# 08_LMS1_RF.net
KiCad netlist of a schematic drawn in Altium Designer
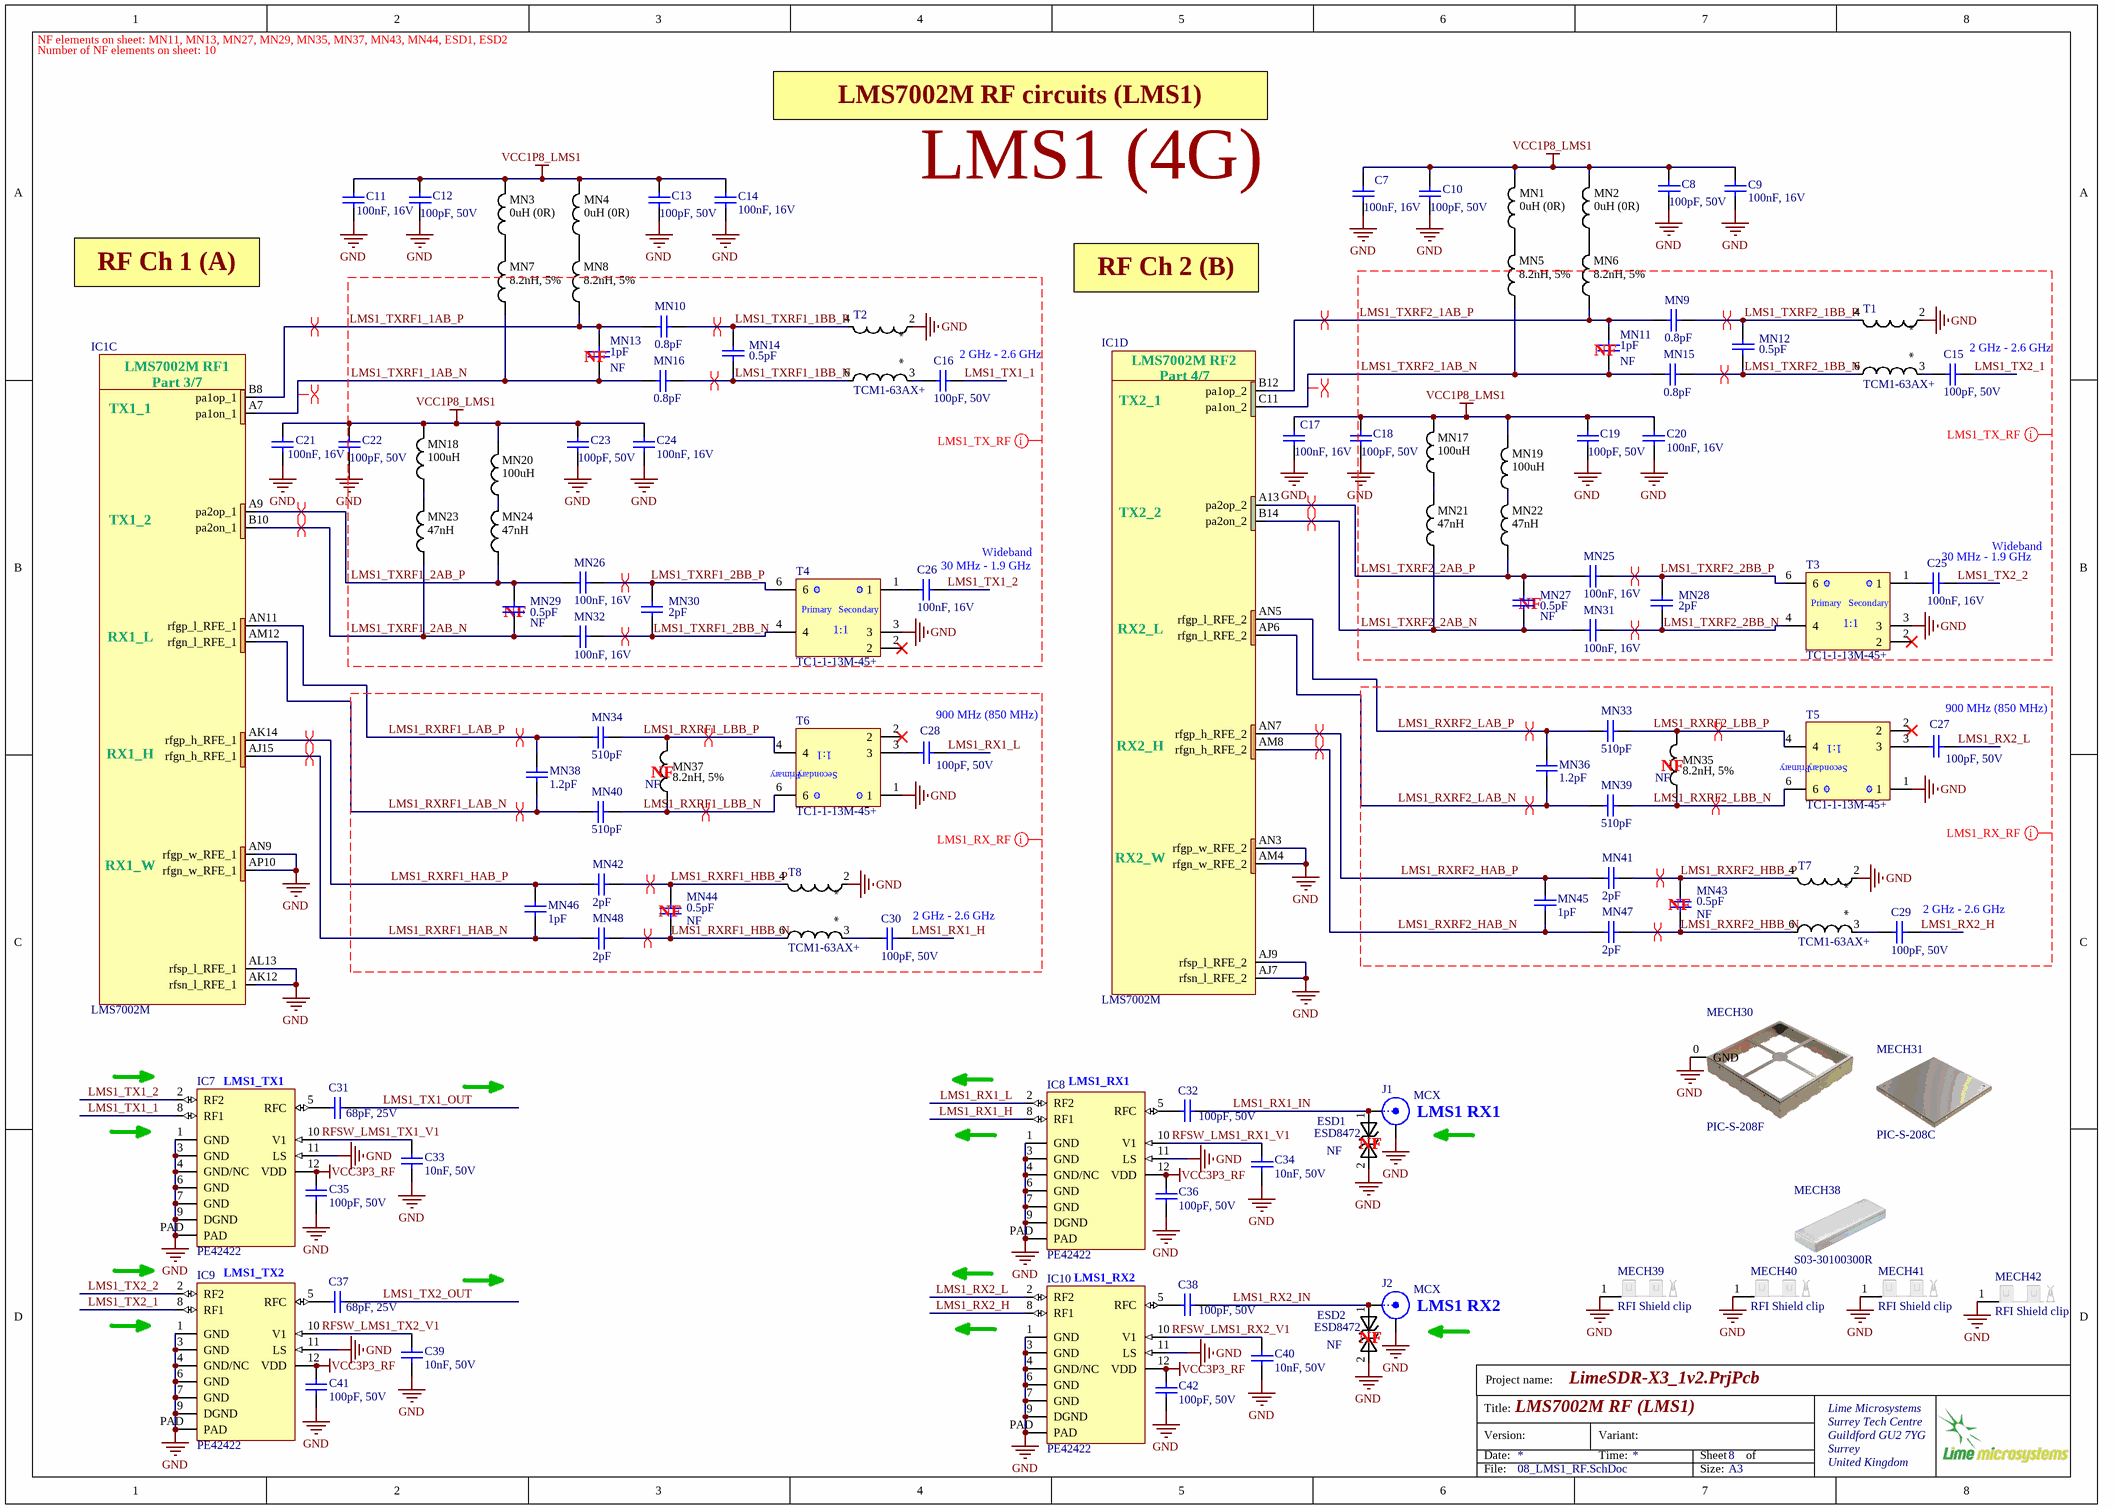
[diagram p0: 08_LMS1_RF.SchDoc]

(export (version "E")
  (design (tool "Eeschema 10.0.6"))
  (components
    (comp (ref "C7")
      (value "100nF, 16V")
      (footprint "CAP0402")
      (fields (field (name "MANUFACTURER") "Murata Electronics") (field (name "TOLERANCE") "10 %"))
      (libsource (lib "") (part "Cap_0402_4"))
    )
    (comp (ref "C8")
      (value "100pF, 50V")
      (footprint "CAP0402")
      (fields (field (name "MANUFACTURER") "Yageo") (field (name "TOLERANCE") "±5%"))
      (libsource (lib "") (part "Cap_0402_3"))
    )
    (comp (ref "C9")
      (value "100nF, 16V")
      (footprint "CAP0402")
      (fields (field (name "MANUFACTURER") "Murata Electronics") (field (name "TOLERANCE") "10 %"))
      (libsource (lib "") (part "Cap_0402_4"))
    )
    (comp (ref "C10")
      (value "100pF, 50V")
      (footprint "CAP0402")
      (fields (field (name "MANUFACTURER") "Yageo") (field (name "TOLERANCE") "±5%"))
      (libsource (lib "") (part "Cap_0402_3"))
    )
    (comp (ref "C11")
      (value "100nF, 16V")
      (footprint "CAP0402")
      (fields (field (name "MANUFACTURER") "Murata Electronics") (field (name "TOLERANCE") "10 %"))
      (libsource (lib "") (part "Cap_0402_4"))
    )
    (comp (ref "C12")
      (value "100pF, 50V")
      (footprint "CAP0402")
      (fields (field (name "MANUFACTURER") "Yageo") (field (name "TOLERANCE") "±5%"))
      (libsource (lib "") (part "Cap_0402_3"))
    )
    (comp (ref "C13")
      (value "100pF, 50V")
      (footprint "CAP0402")
      (fields (field (name "MANUFACTURER") "Yageo") (field (name "TOLERANCE") "±5%"))
      (libsource (lib "") (part "Cap_0402_3"))
    )
    (comp (ref "C14")
      (value "100nF, 16V")
      (footprint "CAP0402")
      (fields (field (name "MANUFACTURER") "Murata Electronics") (field (name "TOLERANCE") "10 %"))
      (libsource (lib "") (part "Cap_0402_4"))
    )
    (comp (ref "C15")
      (value "100pF, 50V")
      (footprint "CAP0402")
      (fields (field (name "TOLERANCE") "±5%") (field (name "MANUFACTURER") "Yageo"))
      (libsource (lib "") (part "Cap_0402_8"))
    )
    (comp (ref "C16")
      (value "100pF, 50V")
      (footprint "CAP0402")
      (fields (field (name "TOLERANCE") "±5%") (field (name "MANUFACTURER") "Yageo"))
      (libsource (lib "") (part "Cap_0402_8"))
    )
    (comp (ref "C17")
      (value "100nF, 16V")
      (footprint "CAP0402")
      (fields (field (name "MANUFACTURER") "Murata Electronics") (field (name "TOLERANCE") "10 %"))
      (libsource (lib "") (part "Cap_0402_2"))
    )
    (comp (ref "C18")
      (value "100pF, 50V")
      (footprint "CAP0402")
      (fields (field (name "MANUFACTURER") "Yageo") (field (name "TOLERANCE") "±5%"))
      (libsource (lib "") (part "Cap_0402_3"))
    )
    (comp (ref "C19")
      (value "100pF, 50V")
      (footprint "CAP0402")
      (fields (field (name "MANUFACTURER") "Yageo") (field (name "TOLERANCE") "±5%"))
      (libsource (lib "") (part "Cap_0402_3"))
    )
    (comp (ref "C20")
      (value "100nF, 16V")
      (footprint "CAP0402")
      (fields (field (name "MANUFACTURER") "Murata Electronics") (field (name "TOLERANCE") "10 %"))
      (libsource (lib "") (part "Cap_0402_2"))
    )
    (comp (ref "C21")
      (value "100nF, 16V")
      (footprint "CAP0402")
      (fields (field (name "MANUFACTURER") "Murata Electronics") (field (name "TOLERANCE") "10 %"))
      (libsource (lib "") (part "Cap_0402_2"))
    )
    (comp (ref "C22")
      (value "100pF, 50V")
      (footprint "CAP0402")
      (fields (field (name "MANUFACTURER") "Yageo") (field (name "TOLERANCE") "±5%"))
      (libsource (lib "") (part "Cap_0402_3"))
    )
    (comp (ref "C23")
      (value "100pF, 50V")
      (footprint "CAP0402")
      (fields (field (name "MANUFACTURER") "Yageo") (field (name "TOLERANCE") "±5%"))
      (libsource (lib "") (part "Cap_0402_3"))
    )
    (comp (ref "C24")
      (value "100nF, 16V")
      (footprint "CAP0402")
      (fields (field (name "MANUFACTURER") "Murata Electronics") (field (name "TOLERANCE") "10 %"))
      (libsource (lib "") (part "Cap_0402_2"))
    )
    (comp (ref "C25")
      (value "100nF, 16V")
      (footprint "CAP0402")
      (fields (field (name "MANUFACTURER") "Murata Electronics") (field (name "TOLERANCE") "10 %"))
      (libsource (lib "") (part "Cap_0402_11"))
    )
    (comp (ref "C26")
      (value "100nF, 16V")
      (footprint "CAP0402")
      (fields (field (name "MANUFACTURER") "Murata Electronics") (field (name "TOLERANCE") "10 %"))
      (libsource (lib "") (part "Cap_0402_11"))
    )
    (comp (ref "C27")
      (value "100pF, 50V")
      (footprint "CAP0402")
      (fields (field (name "TOLERANCE") "±5%") (field (name "MANUFACTURER") "Yageo"))
      (libsource (lib "LimeMicroAltiumLib_schLib") (part "Cap_0402"))
    )
    (comp (ref "C28")
      (value "100pF, 50V")
      (footprint "CAP0402")
      (fields (field (name "TOLERANCE") "±5%") (field (name "MANUFACTURER") "Yageo"))
      (libsource (lib "LimeMicroAltiumLib_schLib") (part "Cap_0402"))
    )
    (comp (ref "C29")
      (value "100pF, 50V")
      (footprint "CAP0402")
      (fields (field (name "TOLERANCE") "±5%") (field (name "MANUFACTURER") "Yageo"))
      (libsource (lib "") (part "Cap_0402_9"))
    )
    (comp (ref "C30")
      (value "100pF, 50V")
      (footprint "CAP0402")
      (fields (field (name "TOLERANCE") "±5%") (field (name "MANUFACTURER") "Yageo"))
      (libsource (lib "") (part "Cap_0402_9"))
    )
    (comp (ref "C31")
      (value "68pF, 25V")
      (footprint "CAP0402")
      (fields (field (name "TOLERANCE") "±1%") (field (name "MANUFACTURER") "Kemet"))
      (libsource (lib "") (part "Cap_0402_8"))
    )
    (comp (ref "C32")
      (value "100pF, 50V")
      (footprint "CAP0402")
      (fields (field (name "TOLERANCE") "±5%") (field (name "MANUFACTURER") "Yageo"))
      (libsource (lib "") (part "Cap_0402_6"))
    )
    (comp (ref "C33")
      (value "10nF, 50V")
      (footprint "CAP0402")
      (fields
        (field (name "MANUFACTURER") "Murata Electronics North America")
        (field (name "TOLERANCE") "±10%")
      )
      (libsource (lib "") (part "Cap_0402_4"))
    )
    (comp (ref "C34")
      (value "10nF, 50V")
      (footprint "CAP0402")
      (fields
        (field (name "MANUFACTURER") "Murata Electronics North America")
        (field (name "TOLERANCE") "±10%")
      )
      (libsource (lib "") (part "Cap_0402_2"))
    )
    (comp (ref "C35")
      (value "100pF, 50V")
      (footprint "CAP0402")
      (fields (field (name "TOLERANCE") "±5%") (field (name "MANUFACTURER") "Yageo"))
      (libsource (lib "") (part "Cap_0402_4"))
    )
    (comp (ref "C36")
      (value "100pF, 50V")
      (footprint "CAP0402")
      (fields (field (name "TOLERANCE") "±5%") (field (name "MANUFACTURER") "Yageo"))
      (libsource (lib "") (part "Cap_0402_5"))
    )
    (comp (ref "C37")
      (value "68pF, 25V")
      (footprint "CAP0402")
      (fields (field (name "TOLERANCE") "±1%") (field (name "MANUFACTURER") "Kemet"))
      (libsource (lib "") (part "Cap_0402_8"))
    )
    (comp (ref "C38")
      (value "100pF, 50V")
      (footprint "CAP0402")
      (fields (field (name "TOLERANCE") "±5%") (field (name "MANUFACTURER") "Yageo"))
      (libsource (lib "") (part "Cap_0402_6"))
    )
    (comp (ref "C39")
      (value "10nF, 50V")
      (footprint "CAP0402")
      (fields
        (field (name "MANUFACTURER") "Murata Electronics North America")
        (field (name "TOLERANCE") "±10%")
      )
      (libsource (lib "") (part "Cap_0402_4"))
    )
    (comp (ref "C40")
      (value "10nF, 50V")
      (footprint "CAP0402")
      (fields
        (field (name "MANUFACTURER") "Murata Electronics North America")
        (field (name "TOLERANCE") "±10%")
      )
      (libsource (lib "") (part "Cap_0402_2"))
    )
    (comp (ref "C41")
      (value "100pF, 50V")
      (footprint "CAP0402")
      (fields (field (name "TOLERANCE") "±5%") (field (name "MANUFACTURER") "Yageo"))
      (libsource (lib "") (part "Cap_0402_4"))
    )
    (comp (ref "C42")
      (value "100pF, 50V")
      (footprint "CAP0402")
      (fields (field (name "TOLERANCE") "±5%") (field (name "MANUFACTURER") "Yageo"))
      (libsource (lib "") (part "Cap_0402_5"))
    )
    (comp (ref "ESD1")
      (value "ESD8472")
      (footprint "ESD8472_X3DFN2")
      (fields (field (name "MANUFACTURER") "ON Semiconductor") (field (name "ASSEMBLY INFO") "NF"))
      (libsource (lib "LimeMicroAltiumLib_schLib") (part "ESD8472"))
    )
    (comp (ref "ESD2")
      (value "ESD8472")
      (footprint "ESD8472_X3DFN2")
      (fields (field (name "MANUFACTURER") "ON Semiconductor") (field (name "ASSEMBLY INFO") "NF"))
      (libsource (lib "LimeMicroAltiumLib_schLib") (part "ESD8472"))
    )
    (comp (ref "IC1")
      (value "LMS7002M")
      (footprint "LMS7002M_v5")
      (description "Schematic symbol revision 4. Default footprint - 0.31mm pad")
      (fields (field (name "MANUFACTURER") "Lime Microsystems"))
      (libsource (lib "LimeMicroAltiumLib_schLib_r04") (part "LMS7002Mr4"))
    )
    (comp (ref "IC7")
      (value "PE42422")
      (footprint "PE42422_QFN12")
      (fields (field (name "MANUFACTURER") "Peregrine Semiconductor"))
      (libsource (lib "") (part "PE42422_1"))
    )
    (comp (ref "IC8")
      (value "PE42422")
      (footprint "PE42422_QFN12")
      (fields (field (name "MANUFACTURER") "Peregrine Semiconductor"))
      (libsource (lib "LimeMicroAltiumLib_schLib") (part "PE42422"))
    )
    (comp (ref "IC9")
      (value "PE42422")
      (footprint "PE42422_QFN12")
      (fields (field (name "MANUFACTURER") "Peregrine Semiconductor"))
      (libsource (lib "") (part "PE42422_1"))
    )
    (comp (ref "IC10")
      (value "PE42422")
      (footprint "PE42422_QFN12")
      (fields (field (name "MANUFACTURER") "Peregrine Semiconductor"))
      (libsource (lib "LimeMicroAltiumLib_schLib") (part "PE42422"))
    )
    (comp (ref "J1")
      (value "MCX")
      (footprint "MCX_connector_vertical_SM")
      (fields (field (name "MANUFACTURER") "Bel Cinch"))
      (libsource (lib "LimeMicroAltiumLib_schLib") (part "RF_IF_connector"))
    )
    (comp (ref "J2")
      (value "MCX")
      (footprint "MCX_connector_vertical_SM")
      (fields (field (name "MANUFACTURER") "Bel Cinch"))
      (libsource (lib "LimeMicroAltiumLib_schLib") (part "RF_IF_connector"))
    )
    (comp (ref "MECH30")
      (value "PIC-S-208F")
      (footprint "PIC-S-208F_RF_SHIELD_FRAME_r0")
      (fields (field (name "MANUFACTURER") "3G Shielding Specialties LP"))
      (libsource (lib "LimeMicroAltiumLib") (part "PIC-S-208F_RF_SHIELD_FRAME"))
    )
    (comp (ref "MECH31")
      (value "PIC-S-208C")
      (footprint "PIC-S-208C_RF_SHIELD_COVER")
      (fields (field (name "MANUFACTURER") "3G Shielding Specialties LP"))
      (libsource (lib "LimeMicroAltiumLib") (part "PIC-S-208C_RF_SHIELD_COVER"))
    )
    (comp (ref "MECH38")
      (value "S03-30100300R")
      (footprint "S03-30100300R_RF_SHIELD")
      (fields (field (name "MANUFACTURER") "Harwin"))
      (libsource (lib "LimeMicroAltiumLib") (part "S03-30100300R_RF_SHIELD"))
    )
    (comp (ref "MECH39")
      (value "RFI Shield clip")
      (footprint "RFI_SHIELD_CLPS_MINI")
      (fields (field (name "MANUFACTURER") "HARWIN"))
      (libsource (lib "LimeMicroAltiumLib") (part "RFI_SHIELD_CLIP"))
    )
    (comp (ref "MECH40")
      (value "RFI Shield clip")
      (footprint "RFI_SHIELD_CLPS_MINI")
      (fields (field (name "MANUFACTURER") "HARWIN"))
      (libsource (lib "LimeMicroAltiumLib") (part "RFI_SHIELD_CLIP"))
    )
    (comp (ref "MECH41")
      (value "RFI Shield clip")
      (footprint "RFI_SHIELD_CLPS_MINI")
      (fields (field (name "MANUFACTURER") "HARWIN"))
      (libsource (lib "LimeMicroAltiumLib") (part "RFI_SHIELD_CLIP"))
    )
    (comp (ref "MECH42")
      (value "RFI Shield clip")
      (footprint "RFI_SHIELD_CLPS_MINI")
      (fields (field (name "MANUFACTURER") "HARWIN"))
      (libsource (lib "LimeMicroAltiumLib") (part "RFI_SHIELD_CLIP"))
    )
    (comp (ref "MN1")
      (value "0uH (0R)")
      (footprint "RES0603")
      (fields
        (field (name "MANUFACTURER") "Panasonic Electronic Components")
        (field (name "MANUFACTURER PART NUMBER") "ERJ-3GEY0R00V")
        (field (name "TOLERANCE") "Jumper")
      )
      (libsource (lib "") (part "Inductor_0603_1"))
    )
    (comp (ref "MN2")
      (value "0uH (0R)")
      (footprint "RES0603")
      (fields
        (field (name "MANUFACTURER") "Panasonic Electronic Components")
        (field (name "MANUFACTURER PART NUMBER") "ERJ-3GEY0R00V")
        (field (name "TOLERANCE") "Jumper")
      )
      (libsource (lib "") (part "Inductor_0603_1"))
    )
    (comp (ref "MN3")
      (value "0uH (0R)")
      (footprint "RES0603")
      (fields
        (field (name "MANUFACTURER") "Panasonic Electronic Components")
        (field (name "MANUFACTURER PART NUMBER") "ERJ-3GEY0R00V")
        (field (name "TOLERANCE") "Jumper")
      )
      (libsource (lib "") (part "Inductor_0603_1"))
    )
    (comp (ref "MN4")
      (value "0uH (0R)")
      (footprint "RES0603")
      (fields
        (field (name "MANUFACTURER") "Panasonic Electronic Components")
        (field (name "MANUFACTURER PART NUMBER") "ERJ-3GEY0R00V")
        (field (name "TOLERANCE") "Jumper")
      )
      (libsource (lib "") (part "Inductor_0603_1"))
    )
    (comp (ref "MN5")
      (value "8.2nH, 5%")
      (footprint "RES0402")
      (fields (field (name "MANUFACTURER") "COILCRAFT"))
      (libsource (lib "LimeMicroAltiumLib_schLib") (part "Inductor_0603"))
    )
    (comp (ref "MN6")
      (value "8.2nH, 5%")
      (footprint "RES0402")
      (fields (field (name "MANUFACTURER") "COILCRAFT"))
      (libsource (lib "LimeMicroAltiumLib_schLib") (part "Inductor_0603"))
    )
    (comp (ref "MN7")
      (value "8.2nH, 5%")
      (footprint "RES0402")
      (fields (field (name "MANUFACTURER") "COILCRAFT"))
      (libsource (lib "LimeMicroAltiumLib_schLib") (part "Inductor_0603"))
    )
    (comp (ref "MN8")
      (value "8.2nH, 5%")
      (footprint "RES0402")
      (fields (field (name "MANUFACTURER") "COILCRAFT"))
      (libsource (lib "LimeMicroAltiumLib_schLib") (part "Inductor_0603"))
    )
    (comp (ref "MN9")
      (value "0.8pF")
      (footprint "CAP0402")
      (fields
        (field (name "TOLERANCE") "±0.1pF")
        (field (name "MANUFACTURER") "Murata Electronics North America")
        (field (name "MANUFACTURER PART NUMBER") "GRM1555C1HR80BA01D")
      )
      (libsource (lib "") (part "Cap_0402_1"))
    )
    (comp (ref "MN10")
      (value "0.8pF")
      (footprint "CAP0402")
      (fields
        (field (name "TOLERANCE") "±0.1pF")
        (field (name "MANUFACTURER") "Murata Electronics North America")
        (field (name "MANUFACTURER PART NUMBER") "GRM1555C1HR80BA01D")
      )
      (libsource (lib "") (part "Cap_0402_1"))
    )
    (comp (ref "MN11")
      (value "1pF")
      (footprint "CAP0402")
      (fields
        (field (name "ASSEMBLY INFO") "NF")
        (field (name "MANUFACTURER") "TDK Corporation")
        (field (name "TOLERANCE") "±0.1pF")
      )
      (libsource (lib "LimeMicroAltiumLib_schLib") (part "Cap_0402"))
    )
    (comp (ref "MN12")
      (value "0.5pF")
      (footprint "CAP0402")
      (fields (field (name "TOLERANCE") "±0.25pF") (field (name "MANUFACTURER") "Yageo"))
      (libsource (lib "") (part "Cap_0402_7"))
    )
    (comp (ref "MN13")
      (value "1pF")
      (footprint "CAP0402")
      (fields
        (field (name "ASSEMBLY INFO") "NF")
        (field (name "MANUFACTURER") "TDK Corporation")
        (field (name "TOLERANCE") "±0.1pF")
      )
      (libsource (lib "LimeMicroAltiumLib_schLib") (part "Cap_0402"))
    )
    (comp (ref "MN14")
      (value "0.5pF")
      (footprint "CAP0402")
      (fields (field (name "TOLERANCE") "±0.25pF") (field (name "MANUFACTURER") "Yageo"))
      (libsource (lib "") (part "Cap_0402_7"))
    )
    (comp (ref "MN15")
      (value "0.8pF")
      (footprint "CAP0402")
      (fields
        (field (name "TOLERANCE") "±0.1pF")
        (field (name "MANUFACTURER") "Murata Electronics North America")
        (field (name "MANUFACTURER PART NUMBER") "GRM1555C1HR80BA01D")
      )
      (libsource (lib "") (part "Cap_0402_1"))
    )
    (comp (ref "MN16")
      (value "0.8pF")
      (footprint "CAP0402")
      (fields
        (field (name "TOLERANCE") "±0.1pF")
        (field (name "MANUFACTURER") "Murata Electronics North America")
        (field (name "MANUFACTURER PART NUMBER") "GRM1555C1HR80BA01D")
      )
      (libsource (lib "") (part "Cap_0402_1"))
    )
    (comp (ref "MN17")
      (value "100uH")
      (footprint "RES0603")
      (fields
        (field (name "MANUFACTURER") "TDK Corporation")
        (field (name "MANUFACTURER PART NUMBER") "GLFR1608T101M-LR")
        (field (name "TOLERANCE") "±20%")
      )
      (libsource (lib "") (part "Inductor_0603_1"))
    )
    (comp (ref "MN18")
      (value "100uH")
      (footprint "RES0603")
      (fields
        (field (name "MANUFACTURER") "TDK Corporation")
        (field (name "MANUFACTURER PART NUMBER") "GLFR1608T101M-LR")
        (field (name "TOLERANCE") "±20%")
      )
      (libsource (lib "") (part "Inductor_0603_1"))
    )
    (comp (ref "MN19")
      (value "100uH")
      (footprint "RES0603")
      (fields
        (field (name "MANUFACTURER") "TDK Corporation")
        (field (name "MANUFACTURER PART NUMBER") "GLFR1608T101M-LR")
        (field (name "TOLERANCE") "±20%")
      )
      (libsource (lib "") (part "Inductor_0603_1"))
    )
    (comp (ref "MN20")
      (value "100uH")
      (footprint "RES0603")
      (fields
        (field (name "MANUFACTURER") "TDK Corporation")
        (field (name "MANUFACTURER PART NUMBER") "GLFR1608T101M-LR")
        (field (name "TOLERANCE") "±20%")
      )
      (libsource (lib "") (part "Inductor_0603_1"))
    )
    (comp (ref "MN21")
      (value "47nH")
      (footprint "RES0402")
      (fields (field (name "MANUFACTURER") "COILCRAFT"))
      (libsource (lib "") (part "Inductor_0603_2"))
    )
    (comp (ref "MN22")
      (value "47nH")
      (footprint "RES0402")
      (fields (field (name "MANUFACTURER") "COILCRAFT"))
      (libsource (lib "") (part "Inductor_0603_2"))
    )
    (comp (ref "MN23")
      (value "47nH")
      (footprint "RES0402")
      (fields (field (name "MANUFACTURER") "COILCRAFT"))
      (libsource (lib "") (part "Inductor_0603_2"))
    )
    (comp (ref "MN24")
      (value "47nH")
      (footprint "RES0402")
      (fields (field (name "MANUFACTURER") "COILCRAFT"))
      (libsource (lib "") (part "Inductor_0603_2"))
    )
    (comp (ref "MN25")
      (value "100nF, 16V")
      (footprint "CAP0402")
      (fields (field (name "MANUFACTURER") "Murata Electronics") (field (name "TOLERANCE") "10 %"))
      (libsource (lib "") (part "Cap_0402_3"))
    )
    (comp (ref "MN26")
      (value "100nF, 16V")
      (footprint "CAP0402")
      (fields (field (name "MANUFACTURER") "Murata Electronics") (field (name "TOLERANCE") "10 %"))
      (libsource (lib "") (part "Cap_0402_3"))
    )
    (comp (ref "MN27")
      (value "0.5pF")
      (footprint "CAP0402")
      (fields
        (field (name "ASSEMBLY INFO") "NF")
        (field (name "TOLERANCE") "±0.25pF")
        (field (name "MANUFACTURER") "Yageo")
      )
      (libsource (lib "") (part "Cap_0402_2"))
    )
    (comp (ref "MN28")
      (value "2pF")
      (footprint "CAP0402")
      (fields (field (name "MANUFACTURER PART NUMBER") "04025U2R0BAT2A") (field (name "MANUFACTURER") "AVX"))
      (libsource (lib "") (part "Cap_0402_2"))
    )
    (comp (ref "MN29")
      (value "0.5pF")
      (footprint "CAP0402")
      (fields
        (field (name "ASSEMBLY INFO") "NF")
        (field (name "TOLERANCE") "±0.25pF")
        (field (name "MANUFACTURER") "Yageo")
      )
      (libsource (lib "") (part "Cap_0402_2"))
    )
    (comp (ref "MN30")
      (value "2pF")
      (footprint "CAP0402")
      (fields (field (name "MANUFACTURER PART NUMBER") "04025U2R0BAT2A") (field (name "MANUFACTURER") "AVX"))
      (libsource (lib "") (part "Cap_0402_2"))
    )
    (comp (ref "MN31")
      (value "100nF, 16V")
      (footprint "CAP0402")
      (fields (field (name "MANUFACTURER") "Murata Electronics") (field (name "TOLERANCE") "10 %"))
      (libsource (lib "") (part "Cap_0402_7"))
    )
    (comp (ref "MN32")
      (value "100nF, 16V")
      (footprint "CAP0402")
      (fields (field (name "MANUFACTURER") "Murata Electronics") (field (name "TOLERANCE") "10 %"))
      (libsource (lib "") (part "Cap_0402_7"))
    )
    (comp (ref "MN33")
      (value "510pF")
      (footprint "CAP0402")
      (fields
        (field (name "TOLERANCE") "±5%")
        (field (name "MANUFACTURER") "Murata Electronics North America")
      )
      (libsource (lib "") (part "Cap_0402_4"))
    )
    (comp (ref "MN34")
      (value "510pF")
      (footprint "CAP0402")
      (fields
        (field (name "TOLERANCE") "±5%")
        (field (name "MANUFACTURER") "Murata Electronics North America")
      )
      (libsource (lib "") (part "Cap_0402_4"))
    )
    (comp (ref "MN35")
      (value "8.2nH, 5%")
      (footprint "RES0402")
      (fields (field (name "MANUFACTURER") "COILCRAFT") (field (name "ASSEMBLY INFO") "NF"))
      (libsource (lib "") (part "Inductor_0603_2"))
    )
    (comp (ref "MN36")
      (value "1.2pF")
      (footprint "CAP0402")
      (fields
        (field (name "MANUFACTURER") "Murata Electronics North America")
        (field (name "TOLERANCE") "±0.25pF")
      )
      (libsource (lib "") (part "Cap_0402_10"))
    )
    (comp (ref "MN37")
      (value "8.2nH, 5%")
      (footprint "RES0402")
      (fields (field (name "MANUFACTURER") "COILCRAFT") (field (name "ASSEMBLY INFO") "NF"))
      (libsource (lib "") (part "Inductor_0603_2"))
    )
    (comp (ref "MN38")
      (value "1.2pF")
      (footprint "CAP0402")
      (fields
        (field (name "MANUFACTURER") "Murata Electronics North America")
        (field (name "TOLERANCE") "±0.25pF")
      )
      (libsource (lib "") (part "Cap_0402_10"))
    )
    (comp (ref "MN39")
      (value "510pF")
      (footprint "CAP0402")
      (fields
        (field (name "TOLERANCE") "±5%")
        (field (name "MANUFACTURER") "Murata Electronics North America")
      )
      (libsource (lib "") (part "Cap_0402_4"))
    )
    (comp (ref "MN40")
      (value "510pF")
      (footprint "CAP0402")
      (fields
        (field (name "TOLERANCE") "±5%")
        (field (name "MANUFACTURER") "Murata Electronics North America")
      )
      (libsource (lib "") (part "Cap_0402_4"))
    )
    (comp (ref "MN41")
      (value "2pF")
      (footprint "CAP0402")
      (fields (field (name "MANUFACTURER PART NUMBER") "04025U2R0BAT2A") (field (name "MANUFACTURER") "AVX"))
      (libsource (lib "") (part "Cap_0402_1"))
    )
    (comp (ref "MN42")
      (value "2pF")
      (footprint "CAP0402")
      (fields (field (name "MANUFACTURER PART NUMBER") "04025U2R0BAT2A") (field (name "MANUFACTURER") "AVX"))
      (libsource (lib "") (part "Cap_0402_1"))
    )
    (comp (ref "MN43")
      (value "0.5pF")
      (footprint "CAP0402")
      (fields
        (field (name "ASSEMBLY INFO") "NF")
        (field (name "TOLERANCE") "±0.25pF")
        (field (name "MANUFACTURER") "Yageo")
      )
      (libsource (lib "") (part "Cap_0402_1"))
    )
    (comp (ref "MN44")
      (value "0.5pF")
      (footprint "CAP0402")
      (fields
        (field (name "ASSEMBLY INFO") "NF")
        (field (name "TOLERANCE") "±0.25pF")
        (field (name "MANUFACTURER") "Yageo")
      )
      (libsource (lib "") (part "Cap_0402_1"))
    )
    (comp (ref "MN45")
      (value "1pF")
      (footprint "CAP0402")
      (fields (field (name "MANUFACTURER") "TDK Corporation") (field (name "TOLERANCE") "±0.1pF"))
      (libsource (lib "") (part "Cap_0402_1"))
    )
    (comp (ref "MN46")
      (value "1pF")
      (footprint "CAP0402")
      (fields (field (name "MANUFACTURER") "TDK Corporation") (field (name "TOLERANCE") "±0.1pF"))
      (libsource (lib "") (part "Cap_0402_1"))
    )
    (comp (ref "MN47")
      (value "2pF")
      (footprint "CAP0402")
      (fields (field (name "MANUFACTURER PART NUMBER") "04025U2R0BAT2A") (field (name "MANUFACTURER") "AVX"))
      (libsource (lib "") (part "Cap_0402_1"))
    )
    (comp (ref "MN48")
      (value "2pF")
      (footprint "CAP0402")
      (fields (field (name "MANUFACTURER PART NUMBER") "04025U2R0BAT2A") (field (name "MANUFACTURER") "AVX"))
      (libsource (lib "") (part "Cap_0402_1"))
    )
    (comp (ref "T1")
      (value "TCM1-63AX+")
      (footprint "TCM1-63AX+_v2")
      (fields (field (name "MANUFACTURER") "Mini-circuits"))
      (libsource (lib "") (part "Balun_v2_1"))
    )
    (comp (ref "T2")
      (value "TCM1-63AX+")
      (footprint "TCM1-63AX+_v2")
      (fields (field (name "MANUFACTURER") "Mini-circuits"))
      (libsource (lib "") (part "Balun_v2_1"))
    )
    (comp (ref "T3")
      (value "TC1-1-13M-45+")
      (footprint "TC1-1-13MA+_JA4220-AL_")
      (fields (field (name "MANUFACTURER") "Minicircuits"))
      (libsource (lib "LimeMicroAltiumLib_schLib") (part "TC1-1-13M+"))
    )
    (comp (ref "T4")
      (value "TC1-1-13M-45+")
      (footprint "TC1-1-13MA+_JA4220-AL_")
      (fields (field (name "MANUFACTURER") "Minicircuits"))
      (libsource (lib "LimeMicroAltiumLib_schLib") (part "TC1-1-13M+"))
    )
    (comp (ref "T5")
      (value "TC1-1-13M-45+")
      (footprint "TC1-1-13MA+_JA4220-AL_")
      (fields (field (name "MANUFACTURER") "Minicircuits"))
      (libsource (lib "") (part "TC1-1-13M+_1"))
    )
    (comp (ref "T6")
      (value "TC1-1-13M-45+")
      (footprint "TC1-1-13MA+_JA4220-AL_")
      (fields (field (name "MANUFACTURER") "Minicircuits"))
      (libsource (lib "") (part "TC1-1-13M+_1"))
    )
    (comp (ref "T7")
      (value "TCM1-63AX+")
      (footprint "TCM1-63AX+_v2")
      (fields (field (name "MANUFACTURER") "Mini-circuits"))
      (libsource (lib "LimeMicroAltiumLib_schLib") (part "Balun_v2"))
    )
    (comp (ref "T8")
      (value "TCM1-63AX+")
      (footprint "TCM1-63AX+_v2")
      (fields (field (name "MANUFACTURER") "Mini-circuits"))
      (libsource (lib "LimeMicroAltiumLib_schLib") (part "Balun_v2"))
    )
  )
  (nets
    (net (code "1") (name "/LMS1_RX1_H") (class "Default")
      (node (ref "C30") (pin "1") (pinfunction "1_1") (pintype "passive"))
      (node (ref "IC8") (pin "8") (pinfunction "RF1_8") (pintype "bidirectional"))
    )
    (net (code "2") (name "/LMS1_RX1_IN") (class "Default")
      (node (ref "C32") (pin "1") (pinfunction "1_1") (pintype "passive"))
      (node (ref "ESD1") (pin "1") (pinfunction "1_1") (pintype "passive"))
      (node (ref "J1") (pin "1") (pinfunction "X_1") (pintype "passive"))
    )
    (net (code "3") (name "/LMS1_RX1_L") (class "Default")
      (node (ref "C28") (pin "1") (pinfunction "1_1") (pintype "passive"))
      (node (ref "IC8") (pin "2") (pinfunction "RF2_2") (pintype "bidirectional"))
    )
    (net (code "4") (name "/LMS1_RX2_H") (class "Default")
      (node (ref "C29") (pin "1") (pinfunction "1_1") (pintype "passive"))
      (node (ref "IC10") (pin "8") (pinfunction "RF1_8") (pintype "bidirectional"))
    )
    (net (code "5") (name "/LMS1_RX2_IN") (class "Default")
      (node (ref "C38") (pin "1") (pinfunction "1_1") (pintype "passive"))
      (node (ref "ESD2") (pin "1") (pinfunction "1_1") (pintype "passive"))
      (node (ref "J2") (pin "1") (pinfunction "X_1") (pintype "passive"))
    )
    (net (code "6") (name "/LMS1_RX2_L") (class "Default")
      (node (ref "C27") (pin "1") (pinfunction "1_1") (pintype "passive"))
      (node (ref "IC10") (pin "2") (pinfunction "RF2_2") (pintype "bidirectional"))
    )
    (net (code "7") (name "/LMS1_RXRF1_HAB_N") (class "Default")
      (node (ref "IC1") (pin "AJ15") (pinfunction "rfgn_h_RFE_1_AJ15") (pintype "passive"))
      (node (ref "MN46") (pin "1") (pinfunction "1_1") (pintype "passive"))
      (node (ref "MN48") (pin "2") (pinfunction "2_2") (pintype "passive"))
    )
    (net (code "8") (name "/LMS1_RXRF1_HAB_P") (class "Default")
      (node (ref "IC1") (pin "AK14") (pinfunction "rfgp_h_RFE_1_AK14") (pintype "passive"))
      (node (ref "MN42") (pin "2") (pinfunction "2_2") (pintype "passive"))
      (node (ref "MN46") (pin "2") (pinfunction "2_2") (pintype "passive"))
    )
    (net (code "9") (name "/LMS1_RXRF1_HBB_N") (class "Default")
      (node (ref "MN44") (pin "1") (pinfunction "1_1") (pintype "passive"))
      (node (ref "MN48") (pin "1") (pinfunction "1_1") (pintype "passive"))
      (node (ref "T8") (pin "6") (pinfunction "6_6") (pintype "passive"))
    )
    (net (code "10") (name "/LMS1_RXRF1_HBB_P") (class "Default")
      (node (ref "MN42") (pin "1") (pinfunction "1_1") (pintype "passive"))
      (node (ref "MN44") (pin "2") (pinfunction "2_2") (pintype "passive"))
      (node (ref "T8") (pin "4") (pinfunction "4_4") (pintype "passive"))
    )
    (net (code "11") (name "/LMS1_RXRF1_LAB_N") (class "Default")
      (node (ref "IC1") (pin "AM12") (pinfunction "rfgn_l_RFE_1_AM12") (pintype "passive"))
      (node (ref "MN38") (pin "1") (pinfunction "1_1") (pintype "passive"))
      (node (ref "MN40") (pin "2") (pinfunction "2_2") (pintype "passive"))
    )
    (net (code "12") (name "/LMS1_RXRF1_LAB_P") (class "Default")
      (node (ref "IC1") (pin "AN11") (pinfunction "rfgp_l_RFE_1_AN11") (pintype "passive"))
      (node (ref "MN34") (pin "2") (pinfunction "2_2") (pintype "passive"))
      (node (ref "MN38") (pin "2") (pinfunction "2_2") (pintype "passive"))
    )
    (net (code "13") (name "/LMS1_RXRF1_LBB_N") (class "Default")
      (node (ref "MN37") (pin "1") (pinfunction "1_1") (pintype "passive"))
      (node (ref "MN40") (pin "1") (pinfunction "1_1") (pintype "passive"))
      (node (ref "T6") (pin "6") (pinfunction "6_6") (pintype "passive"))
    )
    (net (code "14") (name "/LMS1_RXRF1_LBB_P") (class "Default")
      (node (ref "MN34") (pin "1") (pinfunction "1_1") (pintype "passive"))
      (node (ref "MN37") (pin "2") (pinfunction "2_2") (pintype "passive"))
      (node (ref "T6") (pin "4") (pinfunction "4_4") (pintype "passive"))
    )
    (net (code "15") (name "/LMS1_RXRF2_HAB_N") (class "Default")
      (node (ref "IC1") (pin "AM8") (pinfunction "rfgn_h_RFE_2_AM8") (pintype "passive"))
      (node (ref "MN45") (pin "1") (pinfunction "1_1") (pintype "passive"))
      (node (ref "MN47") (pin "2") (pinfunction "2_2") (pintype "passive"))
    )
    (net (code "16") (name "/LMS1_RXRF2_HAB_P") (class "Default")
      (node (ref "IC1") (pin "AN7") (pinfunction "rfgp_h_RFE_2_AN7") (pintype "passive"))
      (node (ref "MN41") (pin "2") (pinfunction "2_2") (pintype "passive"))
      (node (ref "MN45") (pin "2") (pinfunction "2_2") (pintype "passive"))
    )
    (net (code "17") (name "/LMS1_RXRF2_HBB_N") (class "Default")
      (node (ref "MN43") (pin "1") (pinfunction "1_1") (pintype "passive"))
      (node (ref "MN47") (pin "1") (pinfunction "1_1") (pintype "passive"))
      (node (ref "T7") (pin "6") (pinfunction "6_6") (pintype "passive"))
    )
    (net (code "18") (name "/LMS1_RXRF2_HBB_P") (class "Default")
      (node (ref "MN41") (pin "1") (pinfunction "1_1") (pintype "passive"))
      (node (ref "MN43") (pin "2") (pinfunction "2_2") (pintype "passive"))
      (node (ref "T7") (pin "4") (pinfunction "4_4") (pintype "passive"))
    )
    (net (code "19") (name "/LMS1_RXRF2_LAB_N") (class "Default")
      (node (ref "IC1") (pin "AP6") (pinfunction "rfgn_l_RFE_2_AP6") (pintype "passive"))
      (node (ref "MN36") (pin "1") (pinfunction "1_1") (pintype "passive"))
      (node (ref "MN39") (pin "2") (pinfunction "2_2") (pintype "passive"))
    )
    (net (code "20") (name "/LMS1_RXRF2_LAB_P") (class "Default")
      (node (ref "IC1") (pin "AN5") (pinfunction "rfgp_l_RFE_2_AN5") (pintype "passive"))
      (node (ref "MN33") (pin "2") (pinfunction "2_2") (pintype "passive"))
      (node (ref "MN36") (pin "2") (pinfunction "2_2") (pintype "passive"))
    )
    (net (code "21") (name "/LMS1_RXRF2_LBB_N") (class "Default")
      (node (ref "MN35") (pin "1") (pinfunction "1_1") (pintype "passive"))
      (node (ref "MN39") (pin "1") (pinfunction "1_1") (pintype "passive"))
      (node (ref "T5") (pin "6") (pinfunction "6_6") (pintype "passive"))
    )
    (net (code "22") (name "/LMS1_RXRF2_LBB_P") (class "Default")
      (node (ref "MN33") (pin "1") (pinfunction "1_1") (pintype "passive"))
      (node (ref "MN35") (pin "2") (pinfunction "2_2") (pintype "passive"))
      (node (ref "T5") (pin "4") (pinfunction "4_4") (pintype "passive"))
    )
    (net (code "23") (name "/LMS1_TX1_1") (class "Default")
      (node (ref "C16") (pin "1") (pinfunction "1_1") (pintype "passive"))
      (node (ref "IC7") (pin "8") (pinfunction "RF1_8") (pintype "bidirectional"))
    )
    (net (code "24") (name "/LMS1_TX1_2") (class "Default")
      (node (ref "C26") (pin "1") (pinfunction "1_1") (pintype "passive"))
      (node (ref "IC7") (pin "2") (pinfunction "RF2_2") (pintype "bidirectional"))
    )
    (net (code "25") (name "/LMS1_TX1_OUT") (class "Default")
      (node (ref "C31") (pin "2") (pinfunction "2_2") (pintype "passive"))
    )
    (net (code "26") (name "/LMS1_TX2_1") (class "Default")
      (node (ref "C15") (pin "1") (pinfunction "1_1") (pintype "passive"))
      (node (ref "IC9") (pin "8") (pinfunction "RF1_8") (pintype "bidirectional"))
    )
    (net (code "27") (name "/LMS1_TX2_2") (class "Default")
      (node (ref "C25") (pin "1") (pinfunction "1_1") (pintype "passive"))
      (node (ref "IC9") (pin "2") (pinfunction "RF2_2") (pintype "bidirectional"))
    )
    (net (code "28") (name "/LMS1_TX2_OUT") (class "Default")
      (node (ref "C37") (pin "2") (pinfunction "2_2") (pintype "passive"))
    )
    (net (code "29") (name "/LMS1_TXRF1_1AB_N") (class "Default")
      (node (ref "IC1") (pin "A7") (pinfunction "pa1on_1_A7") (pintype "passive"))
      (node (ref "MN13") (pin "2") (pinfunction "2_2") (pintype "passive"))
      (node (ref "MN16") (pin "2") (pinfunction "2_2") (pintype "passive"))
      (node (ref "MN7") (pin "1") (pinfunction "1_1") (pintype "passive"))
    )
    (net (code "30") (name "/LMS1_TXRF1_1AB_P") (class "Default")
      (node (ref "IC1") (pin "B8") (pinfunction "pa1op_1_B8") (pintype "passive"))
      (node (ref "MN10") (pin "2") (pinfunction "2_2") (pintype "passive"))
      (node (ref "MN13") (pin "1") (pinfunction "1_1") (pintype "passive"))
      (node (ref "MN8") (pin "1") (pinfunction "1_1") (pintype "passive"))
    )
    (net (code "31") (name "/LMS1_TXRF1_1BB_N") (class "Default")
      (node (ref "MN14") (pin "1") (pinfunction "1_1") (pintype "passive"))
      (node (ref "MN16") (pin "1") (pinfunction "1_1") (pintype "passive"))
      (node (ref "T2") (pin "6") (pinfunction "6_6") (pintype "passive"))
    )
    (net (code "32") (name "/LMS1_TXRF1_1BB_P") (class "Default")
      (node (ref "MN10") (pin "1") (pinfunction "1_1") (pintype "passive"))
      (node (ref "MN14") (pin "2") (pinfunction "2_2") (pintype "passive"))
      (node (ref "T2") (pin "4") (pinfunction "4_4") (pintype "passive"))
    )
    (net (code "33") (name "/LMS1_TXRF1_2AB_N") (class "Default")
      (node (ref "IC1") (pin "B10") (pinfunction "pa2on_1_B10") (pintype "passive"))
      (node (ref "MN23") (pin "1") (pinfunction "1_1") (pintype "passive"))
      (node (ref "MN29") (pin "1") (pinfunction "1_1") (pintype "passive"))
      (node (ref "MN32") (pin "1") (pinfunction "1_1") (pintype "passive"))
    )
    (net (code "34") (name "/LMS1_TXRF1_2AB_P") (class "Default")
      (node (ref "IC1") (pin "A9") (pinfunction "pa2op_1_A9") (pintype "passive"))
      (node (ref "MN24") (pin "1") (pinfunction "1_1") (pintype "passive"))
      (node (ref "MN26") (pin "2") (pinfunction "2_2") (pintype "passive"))
      (node (ref "MN29") (pin "2") (pinfunction "2_2") (pintype "passive"))
    )
    (net (code "35") (name "/LMS1_TXRF1_2BB_N") (class "Default")
      (node (ref "MN30") (pin "1") (pinfunction "1_1") (pintype "passive"))
      (node (ref "MN32") (pin "2") (pinfunction "2_2") (pintype "passive"))
      (node (ref "T4") (pin "4") (pinfunction "4_4") (pintype "passive"))
    )
    (net (code "36") (name "/LMS1_TXRF1_2BB_P") (class "Default")
      (node (ref "MN26") (pin "1") (pinfunction "1_1") (pintype "passive"))
      (node (ref "MN30") (pin "2") (pinfunction "2_2") (pintype "passive"))
      (node (ref "T4") (pin "6") (pinfunction "6_6") (pintype "passive"))
    )
    (net (code "37") (name "/LMS1_TXRF2_1AB_N") (class "Default")
      (node (ref "IC1") (pin "C11") (pinfunction "pa1on_2_C11") (pintype "passive"))
      (node (ref "MN11") (pin "2") (pinfunction "2_2") (pintype "passive"))
      (node (ref "MN15") (pin "2") (pinfunction "2_2") (pintype "passive"))
      (node (ref "MN5") (pin "1") (pinfunction "1_1") (pintype "passive"))
    )
    (net (code "38") (name "/LMS1_TXRF2_1AB_P") (class "Default")
      (node (ref "IC1") (pin "B12") (pinfunction "pa1op_2_B12") (pintype "passive"))
      (node (ref "MN11") (pin "1") (pinfunction "1_1") (pintype "passive"))
      (node (ref "MN6") (pin "1") (pinfunction "1_1") (pintype "passive"))
      (node (ref "MN9") (pin "2") (pinfunction "2_2") (pintype "passive"))
    )
    (net (code "39") (name "/LMS1_TXRF2_1BB_N") (class "Default")
      (node (ref "MN12") (pin "1") (pinfunction "1_1") (pintype "passive"))
      (node (ref "MN15") (pin "1") (pinfunction "1_1") (pintype "passive"))
      (node (ref "T1") (pin "6") (pinfunction "6_6") (pintype "passive"))
    )
    (net (code "40") (name "/LMS1_TXRF2_1BB_P") (class "Default")
      (node (ref "MN12") (pin "2") (pinfunction "2_2") (pintype "passive"))
      (node (ref "MN9") (pin "1") (pinfunction "1_1") (pintype "passive"))
      (node (ref "T1") (pin "4") (pinfunction "4_4") (pintype "passive"))
    )
    (net (code "41") (name "/LMS1_TXRF2_2AB_N") (class "Default")
      (node (ref "IC1") (pin "B14") (pinfunction "pa2on_2_B14") (pintype "passive"))
      (node (ref "MN21") (pin "1") (pinfunction "1_1") (pintype "passive"))
      (node (ref "MN27") (pin "1") (pinfunction "1_1") (pintype "passive"))
      (node (ref "MN31") (pin "1") (pinfunction "1_1") (pintype "passive"))
    )
    (net (code "42") (name "/LMS1_TXRF2_2AB_P") (class "Default")
      (node (ref "IC1") (pin "A13") (pinfunction "pa2op_2_A13") (pintype "passive"))
      (node (ref "MN22") (pin "1") (pinfunction "1_1") (pintype "passive"))
      (node (ref "MN25") (pin "2") (pinfunction "2_2") (pintype "passive"))
      (node (ref "MN27") (pin "2") (pinfunction "2_2") (pintype "passive"))
    )
    (net (code "43") (name "/LMS1_TXRF2_2BB_N") (class "Default")
      (node (ref "MN28") (pin "1") (pinfunction "1_1") (pintype "passive"))
      (node (ref "MN31") (pin "2") (pinfunction "2_2") (pintype "passive"))
      (node (ref "T3") (pin "4") (pinfunction "4_4") (pintype "passive"))
    )
    (net (code "44") (name "/LMS1_TXRF2_2BB_P") (class "Default")
      (node (ref "MN25") (pin "1") (pinfunction "1_1") (pintype "passive"))
      (node (ref "MN28") (pin "2") (pinfunction "2_2") (pintype "passive"))
      (node (ref "T3") (pin "6") (pinfunction "6_6") (pintype "passive"))
    )
    (net (code "45") (name "/RFSW_LMS1_RX1_V1") (class "Default")
      (node (ref "C34") (pin "1") (pinfunction "1_1") (pintype "passive"))
      (node (ref "IC8") (pin "10") (pinfunction "V1_10") (pintype "input"))
    )
    (net (code "46") (name "/RFSW_LMS1_RX2_V1") (class "Default")
      (node (ref "C40") (pin "1") (pinfunction "1_1") (pintype "passive"))
      (node (ref "IC10") (pin "10") (pinfunction "V1_10") (pintype "input"))
    )
    (net (code "47") (name "/RFSW_LMS1_TX1_V1") (class "Default")
      (node (ref "C33") (pin "1") (pinfunction "1_1") (pintype "passive"))
      (node (ref "IC7") (pin "10") (pinfunction "V1_10") (pintype "input"))
    )
    (net (code "48") (name "/RFSW_LMS1_TX2_V1") (class "Default")
      (node (ref "C39") (pin "1") (pinfunction "1_1") (pintype "passive"))
      (node (ref "IC9") (pin "10") (pinfunction "V1_10") (pintype "input"))
    )
    (net (code "49") (name "GND") (class "Default")
      (node (ref "C10") (pin "1") (pinfunction "1_1") (pintype "passive"))
      (node (ref "C11") (pin "1") (pinfunction "1_1") (pintype "passive"))
      (node (ref "C12") (pin "1") (pinfunction "1_1") (pintype "passive"))
      (node (ref "C13") (pin "1") (pinfunction "1_1") (pintype "passive"))
      (node (ref "C14") (pin "1") (pinfunction "1_1") (pintype "passive"))
      (node (ref "C17") (pin "1") (pinfunction "1_1") (pintype "passive"))
      (node (ref "C18") (pin "1") (pinfunction "1_1") (pintype "passive"))
      (node (ref "C19") (pin "1") (pinfunction "1_1") (pintype "passive"))
      (node (ref "C20") (pin "1") (pinfunction "1_1") (pintype "passive"))
      (node (ref "C21") (pin "1") (pinfunction "1_1") (pintype "passive"))
      (node (ref "C22") (pin "1") (pinfunction "1_1") (pintype "passive"))
      (node (ref "C23") (pin "1") (pinfunction "1_1") (pintype "passive"))
      (node (ref "C24") (pin "1") (pinfunction "1_1") (pintype "passive"))
      (node (ref "C33") (pin "2") (pinfunction "2_2") (pintype "passive"))
      (node (ref "C34") (pin "2") (pinfunction "2_2") (pintype "passive"))
      (node (ref "C35") (pin "1") (pinfunction "1_1") (pintype "passive"))
      (node (ref "C36") (pin "1") (pinfunction "1_1") (pintype "passive"))
      (node (ref "C39") (pin "2") (pinfunction "2_2") (pintype "passive"))
      (node (ref "C40") (pin "2") (pinfunction "2_2") (pintype "passive"))
      (node (ref "C41") (pin "1") (pinfunction "1_1") (pintype "passive"))
      (node (ref "C42") (pin "1") (pinfunction "1_1") (pintype "passive"))
      (node (ref "C7") (pin "1") (pinfunction "1_1") (pintype "passive"))
      (node (ref "C8") (pin "1") (pinfunction "1_1") (pintype "passive"))
      (node (ref "C9") (pin "1") (pinfunction "1_1") (pintype "passive"))
      (node (ref "ESD1") (pin "2") (pinfunction "2_2") (pintype "passive"))
      (node (ref "ESD2") (pin "2") (pinfunction "2_2") (pintype "passive"))
      (node (ref "IC1") (pin "AJ7") (pinfunction "rfsn_l_RFE_2_AJ7") (pintype "passive"))
      (node (ref "IC1") (pin "AJ9") (pinfunction "rfsp_l_RFE_2_AJ9") (pintype "passive"))
      (node (ref "IC1") (pin "AK12") (pinfunction "rfsn_l_RFE_1_AK12") (pintype "passive"))
      (node (ref "IC1") (pin "AL13") (pinfunction "rfsp_l_RFE_1_AL13") (pintype "passive"))
      (node (ref "IC1") (pin "AM4") (pinfunction "rfgn_w_RFE_2_AM4") (pintype "passive"))
      (node (ref "IC1") (pin "AN3") (pinfunction "rfgp_w_RFE_2_AN3") (pintype "passive"))
      (node (ref "IC1") (pin "AN9") (pinfunction "rfgp_w_RFE_1_AN9") (pintype "passive"))
      (node (ref "IC1") (pin "AP10") (pinfunction "rfgn_w_RFE_1_AP10") (pintype "passive"))
      (node (ref "IC10") (pin "1") (pinfunction "GND_1") (pintype "passive"))
      (node (ref "IC10") (pin "11") (pinfunction "LS_11") (pintype "input"))
      (node (ref "IC10") (pin "3") (pinfunction "GND_3") (pintype "passive"))
      (node (ref "IC10") (pin "4") (pinfunction "GND/NC_4") (pintype "passive"))
      (node (ref "IC10") (pin "6") (pinfunction "GND_6") (pintype "passive"))
      (node (ref "IC10") (pin "7") (pinfunction "GND_7") (pintype "passive"))
      (node (ref "IC10") (pin "9") (pinfunction "DGND_9") (pintype "passive"))
      (node (ref "IC10") (pin "PAD") (pinfunction "PAD_PAD") (pintype "passive"))
      (node (ref "IC7") (pin "1") (pinfunction "GND_1") (pintype "passive"))
      (node (ref "IC7") (pin "11") (pinfunction "LS_11") (pintype "input"))
      (node (ref "IC7") (pin "3") (pinfunction "GND_3") (pintype "passive"))
      (node (ref "IC7") (pin "4") (pinfunction "GND/NC_4") (pintype "passive"))
      (node (ref "IC7") (pin "6") (pinfunction "GND_6") (pintype "passive"))
      (node (ref "IC7") (pin "7") (pinfunction "GND_7") (pintype "passive"))
      (node (ref "IC7") (pin "9") (pinfunction "DGND_9") (pintype "passive"))
      (node (ref "IC7") (pin "PAD") (pinfunction "PAD_PAD") (pintype "passive"))
      (node (ref "IC8") (pin "1") (pinfunction "GND_1") (pintype "passive"))
      (node (ref "IC8") (pin "11") (pinfunction "LS_11") (pintype "input"))
      (node (ref "IC8") (pin "3") (pinfunction "GND_3") (pintype "passive"))
      (node (ref "IC8") (pin "4") (pinfunction "GND/NC_4") (pintype "passive"))
      (node (ref "IC8") (pin "6") (pinfunction "GND_6") (pintype "passive"))
      (node (ref "IC8") (pin "7") (pinfunction "GND_7") (pintype "passive"))
      (node (ref "IC8") (pin "9") (pinfunction "DGND_9") (pintype "passive"))
      (node (ref "IC8") (pin "PAD") (pinfunction "PAD_PAD") (pintype "passive"))
      (node (ref "IC9") (pin "1") (pinfunction "GND_1") (pintype "passive"))
      (node (ref "IC9") (pin "11") (pinfunction "LS_11") (pintype "input"))
      (node (ref "IC9") (pin "3") (pinfunction "GND_3") (pintype "passive"))
      (node (ref "IC9") (pin "4") (pinfunction "GND/NC_4") (pintype "passive"))
      (node (ref "IC9") (pin "6") (pinfunction "GND_6") (pintype "passive"))
      (node (ref "IC9") (pin "7") (pinfunction "GND_7") (pintype "passive"))
      (node (ref "IC9") (pin "9") (pinfunction "DGND_9") (pintype "passive"))
      (node (ref "IC9") (pin "PAD") (pinfunction "PAD_PAD") (pintype "passive"))
      (node (ref "J1") (pin "2") (pinfunction "Y_2") (pintype "passive"))
      (node (ref "J2") (pin "2") (pinfunction "Y_2") (pintype "passive"))
      (node (ref "MECH30") (pin "0") (pinfunction "GND_0") (pintype "passive"))
      (node (ref "MECH39") (pin "1") (pinfunction "GND_1") (pintype "passive"))
      (node (ref "MECH40") (pin "1") (pinfunction "GND_1") (pintype "passive"))
      (node (ref "MECH41") (pin "1") (pinfunction "GND_1") (pintype "passive"))
      (node (ref "MECH42") (pin "1") (pinfunction "GND_1") (pintype "passive"))
      (node (ref "T1") (pin "2") (pinfunction "2_2") (pintype "passive"))
      (node (ref "T2") (pin "2") (pinfunction "2_2") (pintype "passive"))
      (node (ref "T3") (pin "3") (pinfunction "3_3") (pintype "passive"))
      (node (ref "T4") (pin "3") (pinfunction "3_3") (pintype "passive"))
      (node (ref "T5") (pin "1") (pinfunction "1_1") (pintype "passive"))
      (node (ref "T6") (pin "1") (pinfunction "1_1") (pintype "passive"))
      (node (ref "T7") (pin "2") (pinfunction "2_2") (pintype "passive"))
      (node (ref "T8") (pin "2") (pinfunction "2_2") (pintype "passive"))
    )
    (net (code "50") (name "Net-(C15-Pad2)") (class "Default")
      (node (ref "C15") (pin "2") (pinfunction "2_2") (pintype "passive"))
      (node (ref "T1") (pin "3") (pinfunction "3_3") (pintype "passive"))
    )
    (net (code "51") (name "Net-(C16-Pad2)") (class "Default")
      (node (ref "C16") (pin "2") (pinfunction "2_2") (pintype "passive"))
      (node (ref "T2") (pin "3") (pinfunction "3_3") (pintype "passive"))
    )
    (net (code "52") (name "Net-(C25-Pad2)") (class "Default")
      (node (ref "C25") (pin "2") (pinfunction "2_2") (pintype "passive"))
      (node (ref "T3") (pin "1") (pinfunction "1_1") (pintype "passive"))
    )
    (net (code "53") (name "Net-(C26-Pad2)") (class "Default")
      (node (ref "C26") (pin "2") (pinfunction "2_2") (pintype "passive"))
      (node (ref "T4") (pin "1") (pinfunction "1_1") (pintype "passive"))
    )
    (net (code "54") (name "Net-(C27-Pad2)") (class "Default")
      (node (ref "C27") (pin "2") (pinfunction "2_2") (pintype "passive"))
      (node (ref "T5") (pin "3") (pinfunction "3_3") (pintype "passive"))
    )
    (net (code "55") (name "Net-(C28-Pad2)") (class "Default")
      (node (ref "C28") (pin "2") (pinfunction "2_2") (pintype "passive"))
      (node (ref "T6") (pin "3") (pinfunction "3_3") (pintype "passive"))
    )
    (net (code "56") (name "Net-(C29-Pad2)") (class "Default")
      (node (ref "C29") (pin "2") (pinfunction "2_2") (pintype "passive"))
      (node (ref "T7") (pin "3") (pinfunction "3_3") (pintype "passive"))
    )
    (net (code "57") (name "Net-(C30-Pad2)") (class "Default")
      (node (ref "C30") (pin "2") (pinfunction "2_2") (pintype "passive"))
      (node (ref "T8") (pin "3") (pinfunction "3_3") (pintype "passive"))
    )
    (net (code "58") (name "Net-(IC7-RFC)") (class "Default")
      (node (ref "C31") (pin "1") (pinfunction "1_1") (pintype "passive"))
      (node (ref "IC7") (pin "5") (pinfunction "RFC_5") (pintype "bidirectional"))
    )
    (net (code "59") (name "Net-(IC8-RFC)") (class "Default")
      (node (ref "C32") (pin "2") (pinfunction "2_2") (pintype "passive"))
      (node (ref "IC8") (pin "5") (pinfunction "RFC_5") (pintype "bidirectional"))
    )
    (net (code "60") (name "Net-(IC9-RFC)") (class "Default")
      (node (ref "C37") (pin "1") (pinfunction "1_1") (pintype "passive"))
      (node (ref "IC9") (pin "5") (pinfunction "RFC_5") (pintype "bidirectional"))
    )
    (net (code "61") (name "Net-(IC10-RFC)") (class "Default")
      (node (ref "C38") (pin "2") (pinfunction "2_2") (pintype "passive"))
      (node (ref "IC10") (pin "5") (pinfunction "RFC_5") (pintype "bidirectional"))
    )
    (net (code "62") (name "Net-(MN1-Pad1)") (class "Default")
      (node (ref "MN1") (pin "1") (pinfunction "1_1") (pintype "passive"))
      (node (ref "MN5") (pin "2") (pinfunction "2_2") (pintype "passive"))
    )
    (net (code "63") (name "Net-(MN2-Pad1)") (class "Default")
      (node (ref "MN2") (pin "1") (pinfunction "1_1") (pintype "passive"))
      (node (ref "MN6") (pin "2") (pinfunction "2_2") (pintype "passive"))
    )
    (net (code "64") (name "Net-(MN3-Pad1)") (class "Default")
      (node (ref "MN3") (pin "1") (pinfunction "1_1") (pintype "passive"))
      (node (ref "MN7") (pin "2") (pinfunction "2_2") (pintype "passive"))
    )
    (net (code "65") (name "Net-(MN4-Pad1)") (class "Default")
      (node (ref "MN4") (pin "1") (pinfunction "1_1") (pintype "passive"))
      (node (ref "MN8") (pin "2") (pinfunction "2_2") (pintype "passive"))
    )
    (net (code "66") (name "Net-(MN17-Pad1)") (class "Default")
      (node (ref "MN17") (pin "1") (pinfunction "1_1") (pintype "passive"))
      (node (ref "MN21") (pin "2") (pinfunction "2_2") (pintype "passive"))
    )
    (net (code "67") (name "Net-(MN18-Pad1)") (class "Default")
      (node (ref "MN18") (pin "1") (pinfunction "1_1") (pintype "passive"))
      (node (ref "MN23") (pin "2") (pinfunction "2_2") (pintype "passive"))
    )
    (net (code "68") (name "Net-(MN19-Pad1)") (class "Default")
      (node (ref "MN19") (pin "1") (pinfunction "1_1") (pintype "passive"))
      (node (ref "MN22") (pin "2") (pinfunction "2_2") (pintype "passive"))
    )
    (net (code "69") (name "Net-(MN20-Pad1)") (class "Default")
      (node (ref "MN20") (pin "1") (pinfunction "1_1") (pintype "passive"))
      (node (ref "MN24") (pin "2") (pinfunction "2_2") (pintype "passive"))
    )
    (net (code "70") (name "VCC1P8_LMS1") (class "Default")
      (node (ref "C10") (pin "2") (pinfunction "2_2") (pintype "passive"))
      (node (ref "C11") (pin "2") (pinfunction "2_2") (pintype "passive"))
      (node (ref "C12") (pin "2") (pinfunction "2_2") (pintype "passive"))
      (node (ref "C13") (pin "2") (pinfunction "2_2") (pintype "passive"))
      (node (ref "C14") (pin "2") (pinfunction "2_2") (pintype "passive"))
      (node (ref "C17") (pin "2") (pinfunction "2_2") (pintype "passive"))
      (node (ref "C18") (pin "2") (pinfunction "2_2") (pintype "passive"))
      (node (ref "C19") (pin "2") (pinfunction "2_2") (pintype "passive"))
      (node (ref "C20") (pin "2") (pinfunction "2_2") (pintype "passive"))
      (node (ref "C21") (pin "2") (pinfunction "2_2") (pintype "passive"))
      (node (ref "C22") (pin "2") (pinfunction "2_2") (pintype "passive"))
      (node (ref "C23") (pin "2") (pinfunction "2_2") (pintype "passive"))
      (node (ref "C24") (pin "2") (pinfunction "2_2") (pintype "passive"))
      (node (ref "C7") (pin "2") (pinfunction "2_2") (pintype "passive"))
      (node (ref "C8") (pin "2") (pinfunction "2_2") (pintype "passive"))
      (node (ref "C9") (pin "2") (pinfunction "2_2") (pintype "passive"))
      (node (ref "MN1") (pin "2") (pinfunction "2_2") (pintype "passive"))
      (node (ref "MN17") (pin "2") (pinfunction "2_2") (pintype "passive"))
      (node (ref "MN18") (pin "2") (pinfunction "2_2") (pintype "passive"))
      (node (ref "MN19") (pin "2") (pinfunction "2_2") (pintype "passive"))
      (node (ref "MN2") (pin "2") (pinfunction "2_2") (pintype "passive"))
      (node (ref "MN20") (pin "2") (pinfunction "2_2") (pintype "passive"))
      (node (ref "MN3") (pin "2") (pinfunction "2_2") (pintype "passive"))
      (node (ref "MN4") (pin "2") (pinfunction "2_2") (pintype "passive"))
    )
    (net (code "71") (name "VCC3P3_RF") (class "Default")
      (node (ref "C35") (pin "2") (pinfunction "2_2") (pintype "passive"))
      (node (ref "C36") (pin "2") (pinfunction "2_2") (pintype "passive"))
      (node (ref "C41") (pin "2") (pinfunction "2_2") (pintype "passive"))
      (node (ref "C42") (pin "2") (pinfunction "2_2") (pintype "passive"))
      (node (ref "IC10") (pin "12") (pinfunction "VDD_12") (pintype "power_in"))
      (node (ref "IC7") (pin "12") (pinfunction "VDD_12") (pintype "power_in"))
      (node (ref "IC8") (pin "12") (pinfunction "VDD_12") (pintype "power_in"))
      (node (ref "IC9") (pin "12") (pinfunction "VDD_12") (pintype "power_in"))
    )
    (net (code "72") (name "unconnected-(T3-Pad2)") (class "Default")
      (node (ref "T3") (pin "2") (pinfunction "2_2") (pintype "passive+no_connect"))
    )
    (net (code "73") (name "unconnected-(T4-Pad2)") (class "Default")
      (node (ref "T4") (pin "2") (pinfunction "2_2") (pintype "passive+no_connect"))
    )
    (net (code "74") (name "unconnected-(T5-Pad2)") (class "Default")
      (node (ref "T5") (pin "2") (pinfunction "2_2") (pintype "passive+no_connect"))
    )
    (net (code "75") (name "unconnected-(T6-Pad2)") (class "Default")
      (node (ref "T6") (pin "2") (pinfunction "2_2") (pintype "passive+no_connect"))
    )
  )
)
